# WS2812B-compact_2.net
KiCad netlist of a schematic drawn in EAGLE
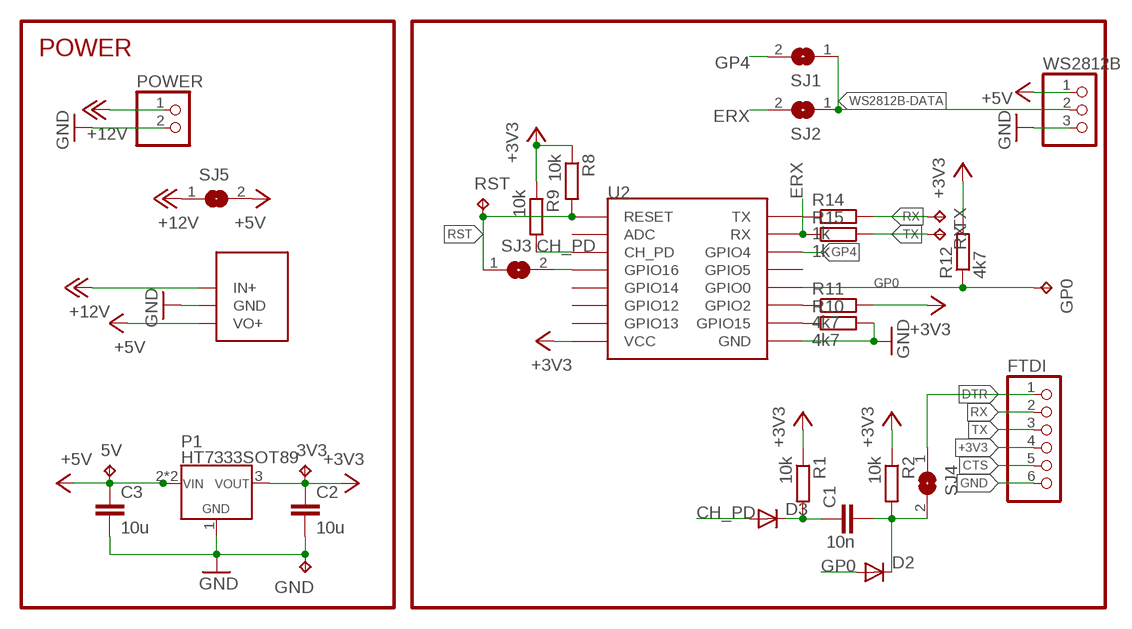
[diagram p0: schematic, sheet 1]

(export (version "E")
  (design (tool "Eeschema 10.0.6"))
  (components
    (comp (ref "3V3")
      (value "TPB1,27")
      (footprint "eagle-import:B1,27")
      (libsource (lib "eagle-import") (part "TPB1,27"))
    )
    (comp (ref "5V")
      (value "TPB1,27")
      (footprint "eagle-import:B1,27")
      (libsource (lib "eagle-import") (part "TPB1,27"))
    )
    (comp (ref "C1")
      (value "10n")
      (footprint "eagle-import:C0805")
      (libsource (lib "eagle-import") (part "C-EUC0805"))
    )
    (comp (ref "C2")
      (value "10u")
      (footprint "eagle-import:C0805")
      (libsource (lib "eagle-import") (part "C-EUC0805"))
    )
    (comp (ref "C3")
      (value "10u")
      (footprint "eagle-import:C0805")
      (libsource (lib "eagle-import") (part "C-EUC0805"))
    )
    (comp (ref "D2")
      (value "DIODE-MINIMELF")
      (footprint "eagle-import:MINIMELF")
      (libsource (lib "eagle-import") (part "DIODE-MINIMELF"))
    )
    (comp (ref "D3")
      (value "DIODE-MINIMELF")
      (footprint "eagle-import:MINIMELF")
      (libsource (lib "eagle-import") (part "DIODE-MINIMELF"))
    )
    (comp (ref "FTDI")
      (value "PINHD-1X06_2.54-S")
      (footprint "eagle-import:1X06-S")
      (libsource (lib "eagle-import") (part "PINHD-1X06_2.54-S"))
    )
    (comp (ref "GND")
      (value "TPB1,27")
      (footprint "eagle-import:B1,27")
      (libsource (lib "eagle-import") (part "TPB1,27"))
    )
    (comp (ref "GP0")
      (value "TPB1,27")
      (footprint "eagle-import:B1,27")
      (libsource (lib "eagle-import") (part "TPB1,27"))
    )
    (comp (ref "P1")
      (value "HT7333SOT89")
      (footprint "eagle-import:SOT89")
      (libsource (lib "eagle-import") (part "HT7333SOT89"))
    )
    (comp (ref "POWER")
      (value "PINHD-1X2")
      (footprint "eagle-import:1X02")
      (libsource (lib "eagle-import") (part "PINHD-1X2"))
    )
    (comp (ref "R1")
      (value "10k")
      (footprint "eagle-import:R0805")
      (libsource (lib "eagle-import") (part "R-EU_R0805"))
    )
    (comp (ref "R2")
      (value "10k")
      (footprint "eagle-import:R0805")
      (libsource (lib "eagle-import") (part "R-EU_R0805"))
    )
    (comp (ref "R8")
      (value "10k")
      (footprint "eagle-import:R0805")
      (libsource (lib "eagle-import") (part "R-EU_R0805"))
    )
    (comp (ref "R9")
      (value "10k")
      (footprint "eagle-import:R0805")
      (libsource (lib "eagle-import") (part "R-EU_R0805"))
    )
    (comp (ref "R10")
      (value "4k7")
      (footprint "eagle-import:R0805")
      (libsource (lib "eagle-import") (part "R-EU_R0805"))
    )
    (comp (ref "R11")
      (value "4k7")
      (footprint "eagle-import:R0805")
      (libsource (lib "eagle-import") (part "R-EU_R0805"))
    )
    (comp (ref "R12")
      (value "4k7")
      (footprint "eagle-import:R0805")
      (libsource (lib "eagle-import") (part "R-EU_R0805"))
    )
    (comp (ref "R14")
      (value "1k")
      (footprint "eagle-import:R0805")
      (libsource (lib "eagle-import") (part "R-EU_R0805"))
    )
    (comp (ref "R15")
      (value "1k")
      (footprint "eagle-import:R0805")
      (libsource (lib "eagle-import") (part "R-EU_R0805"))
    )
    (comp (ref "RST")
      (value "TPB1,27")
      (footprint "eagle-import:B1,27")
      (libsource (lib "eagle-import") (part "TPB1,27"))
    )
    (comp (ref "RX")
      (value "TPB1,27")
      (footprint "eagle-import:B1,27")
      (libsource (lib "eagle-import") (part "TPB1,27"))
    )
    (comp (ref "SJ1") (value "SJ") (footprint "eagle-import:SJ") (libsource (lib "eagle-import") (part "SJ")))
    (comp (ref "SJ2") (value "SJ") (footprint "eagle-import:SJ") (libsource (lib "eagle-import") (part "SJ")))
    (comp (ref "SJ3") (value "SJ") (footprint "eagle-import:SJ") (libsource (lib "eagle-import") (part "SJ")))
    (comp (ref "SJ4") (value "SJ") (footprint "eagle-import:SJ") (libsource (lib "eagle-import") (part "SJ")))
    (comp (ref "SJ5") (value "SJ") (footprint "eagle-import:SJ") (libsource (lib "eagle-import") (part "SJ")))
    (comp (ref "TX")
      (value "TPB1,27")
      (footprint "eagle-import:B1,27")
      (libsource (lib "eagle-import") (part "TPB1,27"))
    )
    (comp (ref "U$1")
      (value "BUCK_CONVERTER_TE818_VAR")
      (footprint "eagle-import:BUCK_CONVERTER_TE818_VAR")
      (libsource (lib "eagle-import") (part "BUCK_CONVERTER_TE818_VAR"))
    )
    (comp (ref "U2")
      (value "ESP12SMD")
      (footprint "eagle-import:ESP12-SMD")
      (libsource (lib "eagle-import") (part "ESP12SMD"))
    )
    (comp (ref "WS2812B")
      (value "PINHD-1X03_2.54-S")
      (footprint "eagle-import:1X03-S")
      (libsource (lib "eagle-import") (part "PINHD-1X03_2.54-S"))
    )
  )
  (nets
    (net (code "1") (name "+3V3") (class "Default")
      (node (ref "3V3") (pin "TP") (pinfunction "TP_TP") (pintype "input"))
      (node (ref "C2") (pin "1") (pinfunction "1_1") (pintype "passive"))
      (node (ref "FTDI") (pin "4") (pinfunction "4_4") (pintype "passive"))
      (node (ref "P1") (pin "3") (pinfunction "VOUT_3") (pintype "power_in"))
      (node (ref "R1") (pin "1") (pinfunction "1_1") (pintype "passive"))
      (node (ref "R11") (pin "2") (pinfunction "2_2") (pintype "passive"))
      (node (ref "R12") (pin "2") (pinfunction "2_2") (pintype "passive"))
      (node (ref "R2") (pin "1") (pinfunction "1_1") (pintype "passive"))
      (node (ref "R8") (pin "1") (pinfunction "1_1") (pintype "passive"))
      (node (ref "R9") (pin "1") (pinfunction "1_1") (pintype "passive"))
      (node (ref "U2") (pin "VCC") (pinfunction "VCC_VCC") (pintype "bidirectional"))
    )
    (net (code "2") (name "+5V") (class "Default")
      (node (ref "5V") (pin "TP") (pinfunction "TP_TP") (pintype "input"))
      (node (ref "C3") (pin "1") (pinfunction "1_1") (pintype "passive"))
      (node (ref "P1") (pin "2") (pinfunction "VIN_2") (pintype "power_in"))
      (node (ref "P1") (pin "2@1") (pinfunction "VIN_2@1") (pintype "power_in"))
      (node (ref "SJ5") (pin "2") (pinfunction "2_2") (pintype "passive"))
      (node (ref "U$1") (pin "VO+") (pinfunction "VO+_VO+") (pintype "bidirectional"))
      (node (ref "WS2812B") (pin "1") (pinfunction "1_1") (pintype "passive"))
    )
    (net (code "3") (name "+12V") (class "Default")
      (node (ref "POWER") (pin "1") (pinfunction "1_1") (pintype "passive"))
      (node (ref "SJ5") (pin "1") (pinfunction "1_1") (pintype "passive"))
      (node (ref "U$1") (pin "IN+") (pinfunction "IN+_IN+") (pintype "bidirectional"))
    )
    (net (code "4") (name "/CH_PD") (class "Default")
      (node (ref "D3") (pin "A") (pinfunction "A_A") (pintype "passive"))
      (node (ref "R9") (pin "2") (pinfunction "2_2") (pintype "passive"))
      (node (ref "U2") (pin "CH_PD") (pinfunction "CH_PD_CH_PD") (pintype "bidirectional"))
    )
    (net (code "5") (name "/ERX") (class "Default")
      (node (ref "R15") (pin "1") (pinfunction "1_1") (pintype "passive"))
      (node (ref "SJ2") (pin "2") (pinfunction "2_2") (pintype "passive"))
      (node (ref "U2") (pin "RXD0") (pinfunction "RX_RXD0") (pintype "bidirectional"))
    )
    (net (code "6") (name "/GP0") (class "Default")
      (node (ref "D2") (pin "A") (pinfunction "A_A") (pintype "passive"))
      (node (ref "GP0") (pin "TP") (pinfunction "TP_TP") (pintype "input"))
      (node (ref "R12") (pin "1") (pinfunction "1_1") (pintype "passive"))
      (node (ref "U2") (pin "GPIO0") (pinfunction "GPIO0_GPIO0") (pintype "bidirectional"))
    )
    (net (code "7") (name "CTS") (class "Default")
      (node (ref "FTDI") (pin "5") (pinfunction "5_5") (pintype "passive"))
    )
    (net (code "8") (name "DTR") (class "Default")
      (node (ref "FTDI") (pin "1") (pinfunction "1_1") (pintype "passive"))
      (node (ref "SJ4") (pin "1") (pinfunction "1_1") (pintype "passive"))
    )
    (net (code "9") (name "GND") (class "Default")
      (node (ref "C2") (pin "2") (pinfunction "2_2") (pintype "passive"))
      (node (ref "C3") (pin "2") (pinfunction "2_2") (pintype "passive"))
      (node (ref "FTDI") (pin "6") (pinfunction "6_6") (pintype "passive"))
      (node (ref "GND") (pin "TP") (pinfunction "TP_TP") (pintype "input"))
      (node (ref "P1") (pin "1") (pinfunction "GND_1") (pintype "power_in"))
      (node (ref "POWER") (pin "2") (pinfunction "2_2") (pintype "passive"))
      (node (ref "R10") (pin "2") (pinfunction "2_2") (pintype "passive"))
      (node (ref "U$1") (pin "GND") (pinfunction "GND_GND") (pintype "bidirectional"))
      (node (ref "U2") (pin "GND") (pinfunction "GND_GND") (pintype "bidirectional"))
      (node (ref "WS2812B") (pin "3") (pinfunction "3_3") (pintype "passive"))
    )
    (net (code "10") (name "GP4") (class "Default")
      (node (ref "SJ1") (pin "2") (pinfunction "2_2") (pintype "passive"))
      (node (ref "U2") (pin "GPIO4") (pinfunction "GPIO4_GPIO4") (pintype "bidirectional"))
    )
    (net (code "11") (name "Net-(C1-Pad1)") (class "Default")
      (node (ref "C1") (pin "1") (pinfunction "1_1") (pintype "passive"))
      (node (ref "D3") (pin "C") (pinfunction "C_C") (pintype "passive"))
      (node (ref "R1") (pin "2") (pinfunction "2_2") (pintype "passive"))
    )
    (net (code "12") (name "Net-(C1-Pad2)") (class "Default")
      (node (ref "C1") (pin "2") (pinfunction "2_2") (pintype "passive"))
      (node (ref "D2") (pin "C") (pinfunction "C_C") (pintype "passive"))
      (node (ref "R2") (pin "2") (pinfunction "2_2") (pintype "passive"))
      (node (ref "SJ4") (pin "2") (pinfunction "2_2") (pintype "passive"))
    )
    (net (code "13") (name "Net-(R10-Pad1)") (class "Default")
      (node (ref "R10") (pin "1") (pinfunction "1_1") (pintype "passive"))
      (node (ref "U2") (pin "GPIO15") (pinfunction "GPIO15_GPIO15") (pintype "bidirectional"))
    )
    (net (code "14") (name "Net-(R11-Pad1)") (class "Default")
      (node (ref "R11") (pin "1") (pinfunction "1_1") (pintype "passive"))
      (node (ref "U2") (pin "GPIO2") (pinfunction "GPIO2_GPIO2") (pintype "bidirectional"))
    )
    (net (code "15") (name "Net-(SJ3-Pad2)") (class "Default")
      (node (ref "SJ3") (pin "2") (pinfunction "2_2") (pintype "passive"))
      (node (ref "U2") (pin "GPIO16") (pinfunction "GPIO16_GPIO16") (pintype "bidirectional"))
    )
    (net (code "16") (name "Net-(U2-TX)") (class "Default")
      (node (ref "R14") (pin "1") (pinfunction "1_1") (pintype "passive"))
      (node (ref "U2") (pin "TXD0") (pinfunction "TX_TXD0") (pintype "bidirectional"))
    )
    (net (code "17") (name "RST") (class "Default")
      (node (ref "R8") (pin "2") (pinfunction "2_2") (pintype "passive"))
      (node (ref "RST") (pin "TP") (pinfunction "TP_TP") (pintype "input"))
      (node (ref "SJ3") (pin "1") (pinfunction "1_1") (pintype "passive"))
      (node (ref "U2") (pin "RESET") (pinfunction "RESET_RESET") (pintype "bidirectional"))
    )
    (net (code "18") (name "RX") (class "Default")
      (node (ref "FTDI") (pin "2") (pinfunction "2_2") (pintype "passive"))
      (node (ref "R14") (pin "2") (pinfunction "2_2") (pintype "passive"))
      (node (ref "TX") (pin "TP") (pinfunction "TP_TP") (pintype "input"))
    )
    (net (code "19") (name "TX") (class "Default")
      (node (ref "FTDI") (pin "3") (pinfunction "3_3") (pintype "passive"))
      (node (ref "R15") (pin "2") (pinfunction "2_2") (pintype "passive"))
      (node (ref "RX") (pin "TP") (pinfunction "TP_TP") (pintype "input"))
    )
    (net (code "20") (name "WS2812B-DATA") (class "Default")
      (node (ref "SJ1") (pin "1") (pinfunction "1_1") (pintype "passive"))
      (node (ref "SJ2") (pin "1") (pinfunction "1_1") (pintype "passive"))
      (node (ref "WS2812B") (pin "2") (pinfunction "2_2") (pintype "passive"))
    )
    (net (code "21") (name "unconnected-(U2-PadADC)") (class "Default")
      (node (ref "U2") (pin "ADC") (pinfunction "ADC_ADC") (pintype "bidirectional"))
    )
    (net (code "22") (name "unconnected-(U2-PadGPIO5)") (class "Default")
      (node (ref "U2") (pin "GPIO5") (pinfunction "GPIO5_GPIO5") (pintype "bidirectional"))
    )
    (net (code "23") (name "unconnected-(U2-PadGPIO12)") (class "Default")
      (node (ref "U2") (pin "GPIO12") (pinfunction "GPIO12_GPIO12") (pintype "bidirectional"))
    )
    (net (code "24") (name "unconnected-(U2-PadGPIO13)") (class "Default")
      (node (ref "U2") (pin "GPIO13") (pinfunction "GPIO13_GPIO13") (pintype "bidirectional"))
    )
    (net (code "25") (name "unconnected-(U2-PadGPIO14)") (class "Default")
      (node (ref "U2") (pin "GPIO14") (pinfunction "GPIO14_GPIO14") (pintype "bidirectional"))
    )
  )
)
